# roboskin_distance_IMU_WIFI.net
KiCad netlist of a schematic drawn in EAGLE
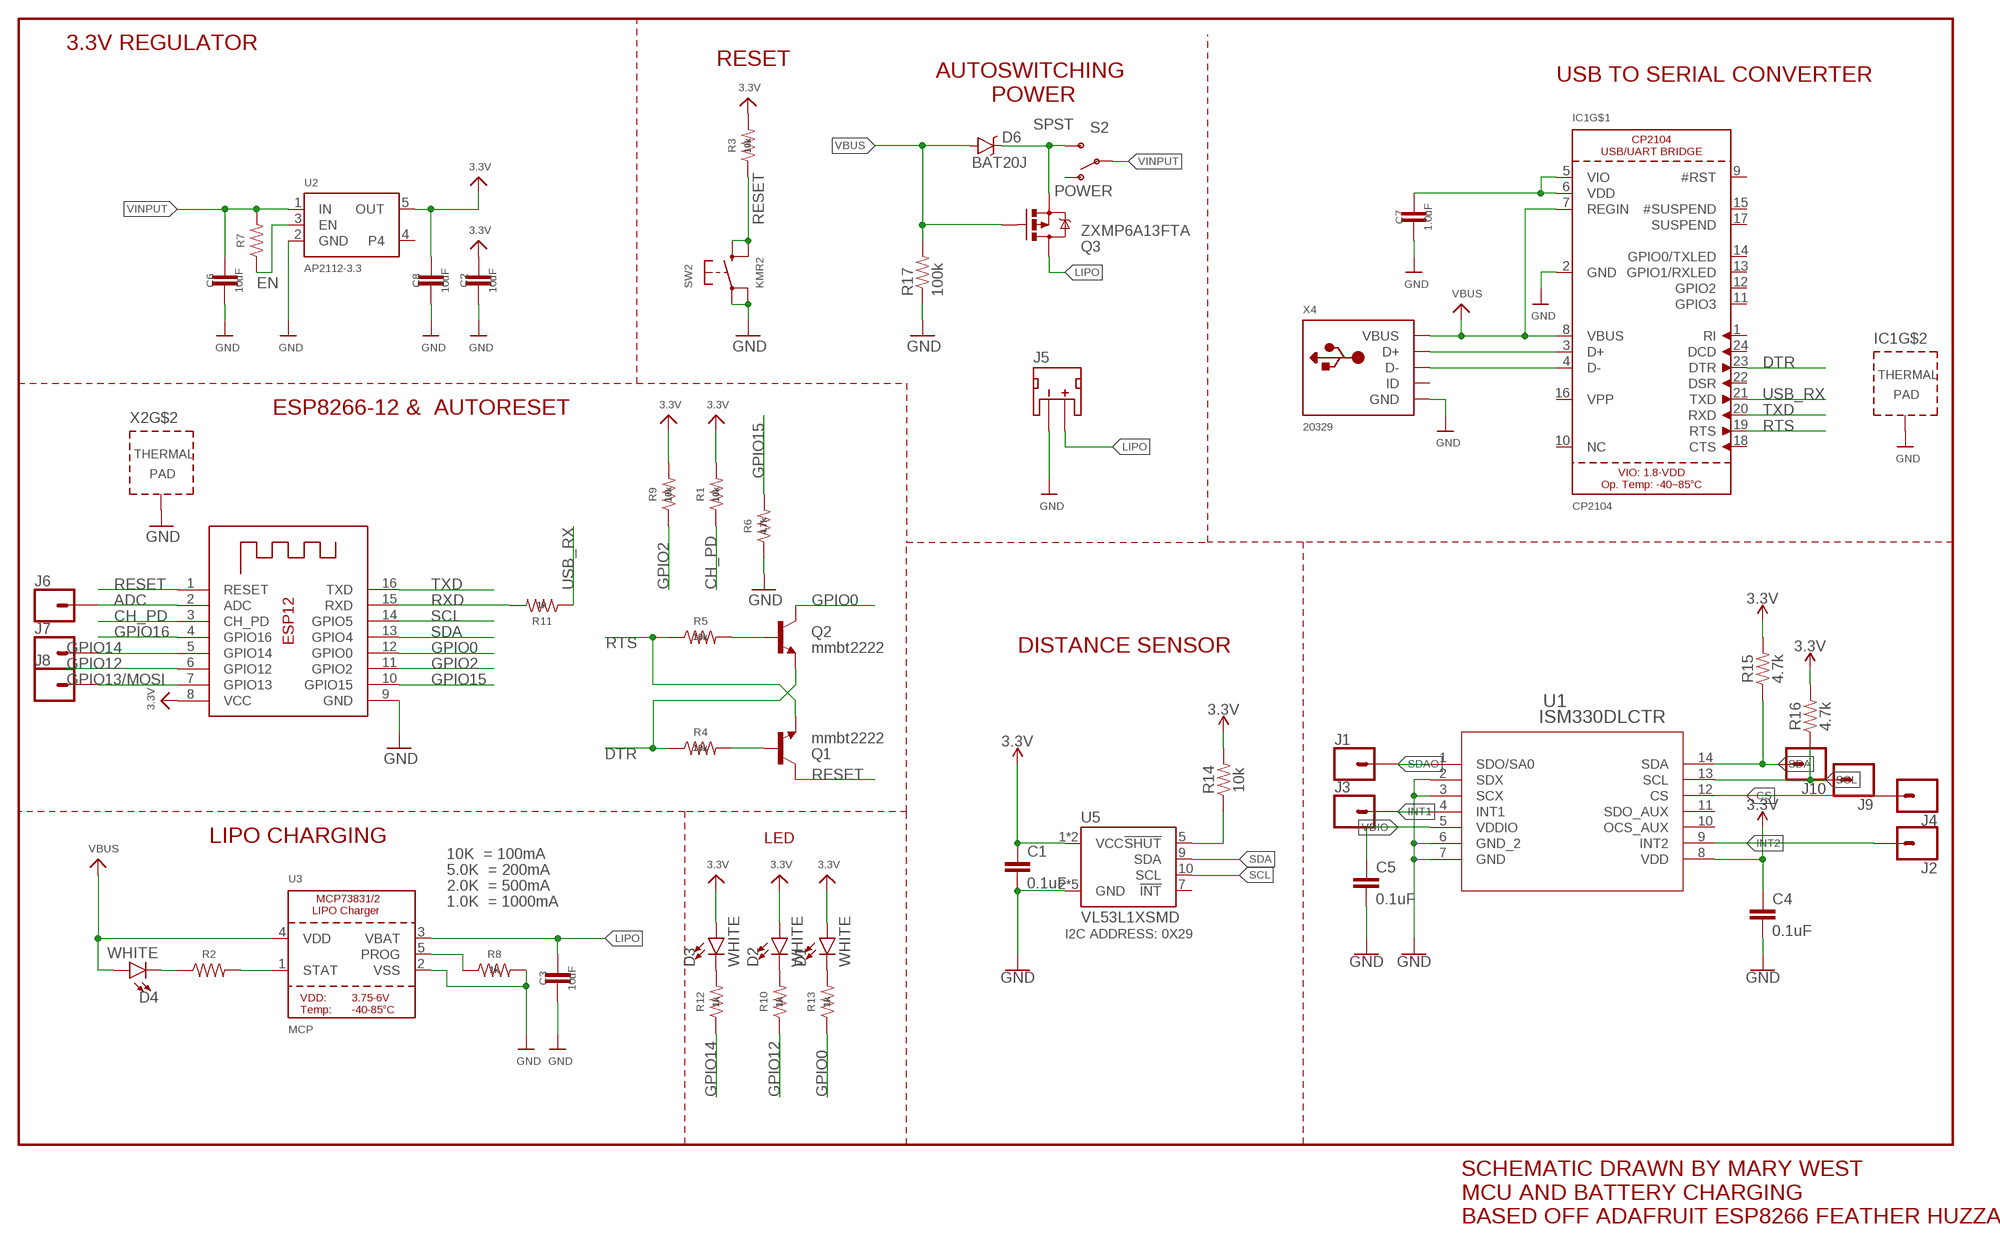
[diagram p0: schematic, sheet 1]

(export (version "E")
  (design (tool "Eeschema 10.0.6"))
  (components
    (comp (ref "C1")
      (value "0.1uF")
      (footprint "eagle-import:0603")
      (libsource (lib "eagle-import") (part "0.1UF-0603-25V-(+80/-20%)"))
    )
    (comp (ref "C2")
      (value "10uF")
      (footprint "eagle-import:0805")
      (libsource (lib "eagle-import") (part "10UF-0805-10V-10%"))
    )
    (comp (ref "C3")
      (value "10uF")
      (footprint "eagle-import:0805")
      (libsource (lib "eagle-import") (part "10UF-0805-10V-10%"))
    )
    (comp (ref "C4")
      (value "0.1uF")
      (footprint "eagle-import:0603")
      (libsource (lib "eagle-import") (part "0.1UF-0603-25V-(+80/-20%)"))
    )
    (comp (ref "C5")
      (value "0.1uF")
      (footprint "eagle-import:0603")
      (libsource (lib "eagle-import") (part "0.1UF-0603-25V-(+80/-20%)"))
    )
    (comp (ref "C6")
      (value "10uF")
      (footprint "eagle-import:0805")
      (libsource (lib "eagle-import") (part "SparkFun-Capacitors_510_10UF-0805-10V-10%"))
    )
    (comp (ref "C7")
      (value "1.0uF")
      (footprint "eagle-import:0603")
      (libsource (lib "eagle-import") (part "1.0UF-0603-16V-10%"))
    )
    (comp (ref "C8")
      (value "10uF")
      (footprint "eagle-import:0805")
      (libsource (lib "eagle-import") (part "10UF-0805-10V-10%"))
    )
    (comp (ref "D1")
      (value "WHITE")
      (footprint "eagle-import:LED-1206")
      (libsource (lib "eagle-import") (part "LED-WHITE1206"))
    )
    (comp (ref "D2")
      (value "WHITE")
      (footprint "eagle-import:LED-1206")
      (libsource (lib "eagle-import") (part "LED-WHITE1206"))
    )
    (comp (ref "D3")
      (value "WHITE")
      (footprint "eagle-import:LED-1206")
      (libsource (lib "eagle-import") (part "LED-WHITE1206"))
    )
    (comp (ref "D4")
      (value "WHITE")
      (footprint "eagle-import:LED-1206")
      (libsource (lib "eagle-import") (part "LED-WHITE1206"))
    )
    (comp (ref "D6")
      (value "BAT20J")
      (footprint "eagle-import:SOD-323")
      (libsource (lib "eagle-import") (part "DIODE-SCHOTTKY-BAT20J"))
    )
    (comp (ref "IC1")
      (value "CP2104")
      (footprint "eagle-import:QFN24_4MM_SMSC")
      (libsource (lib "eagle-import") (part "CP2104"))
    )
    (comp (ref "J1")
      (value "CONN_01")
      (footprint "eagle-import:1X01")
      (libsource (lib "eagle-import") (part "CONN_01"))
    )
    (comp (ref "J2")
      (value "CONN_01")
      (footprint "eagle-import:1X01")
      (libsource (lib "eagle-import") (part "CONN_01"))
    )
    (comp (ref "J3")
      (value "CONN_01")
      (footprint "eagle-import:1X01")
      (libsource (lib "eagle-import") (part "CONN_01"))
    )
    (comp (ref "J4")
      (value "CONN_01")
      (footprint "eagle-import:1X01")
      (libsource (lib "eagle-import") (part "CONN_01"))
    )
    (comp (ref "J5")
      (value "JST_2MM_MALE")
      (footprint "eagle-import:JST-2-SMD")
      (libsource (lib "eagle-import") (part "JST_2MM_MALE"))
    )
    (comp (ref "J6")
      (value "CONN_01")
      (footprint "eagle-import:1X01")
      (libsource (lib "eagle-import") (part "CONN_01"))
    )
    (comp (ref "J7")
      (value "CONN_01")
      (footprint "eagle-import:1X01")
      (libsource (lib "eagle-import") (part "CONN_01"))
    )
    (comp (ref "J8")
      (value "CONN_01")
      (footprint "eagle-import:1X01")
      (libsource (lib "eagle-import") (part "CONN_01"))
    )
    (comp (ref "J9")
      (value "CONN_01")
      (footprint "eagle-import:1X01")
      (libsource (lib "eagle-import") (part "CONN_01"))
    )
    (comp (ref "J10")
      (value "CONN_01")
      (footprint "eagle-import:1X01")
      (libsource (lib "eagle-import") (part "CONN_01"))
    )
    (comp (ref "Q1")
      (value "mmbt2222")
      (footprint "eagle-import:SOT23-3")
      (libsource (lib "eagle-import") (part "TRANSISTOR_NPNSOT23-3"))
    )
    (comp (ref "Q2")
      (value "mmbt2222")
      (footprint "eagle-import:SOT23-3")
      (libsource (lib "eagle-import") (part "TRANSISTOR_NPNSOT23-3"))
    )
    (comp (ref "Q3")
      (value "ZXMP6A13FTA")
      (footprint "eagle-import:SOT23-3")
      (libsource (lib "eagle-import") (part "MOSFET-PCHANNEL"))
    )
    (comp (ref "R1")
      (value "10k")
      (footprint "eagle-import:0603")
      (libsource (lib "eagle-import") (part "SparkFun-Resistors_532_10KOHM-0603-1/10W-1%"))
    )
    (comp (ref "R2")
      (value "1k")
      (footprint "eagle-import:0603")
      (libsource (lib "eagle-import") (part "1KOHM-0603-1/10W-1%"))
    )
    (comp (ref "R3")
      (value "10k")
      (footprint "eagle-import:0603")
      (libsource (lib "eagle-import") (part "SparkFun-Resistors_532_10KOHM-0603-1/10W-1%"))
    )
    (comp (ref "R4")
      (value "10k")
      (footprint "eagle-import:0603")
      (libsource (lib "eagle-import") (part "SparkFun-Resistors_532_10KOHM-0603-1/10W-1%"))
    )
    (comp (ref "R5")
      (value "10k")
      (footprint "eagle-import:0603")
      (libsource (lib "eagle-import") (part "SparkFun-Resistors_532_10KOHM-0603-1/10W-1%"))
    )
    (comp (ref "R6")
      (value "4.7k")
      (footprint "eagle-import:0603")
      (libsource (lib "eagle-import") (part "4.7KOHM-0603-1/10W-1%"))
    )
    (comp (ref "R7")
      (value "10k")
      (footprint "eagle-import:0603")
      (libsource (lib "eagle-import") (part "SparkFun-Resistors_532_10KOHM-0603-1/10W-1%"))
    )
    (comp (ref "R8")
      (value "1k")
      (footprint "eagle-import:0603")
      (libsource (lib "eagle-import") (part "1KOHM-0603-1/10W-1%"))
    )
    (comp (ref "R9")
      (value "10k")
      (footprint "eagle-import:0603")
      (libsource (lib "eagle-import") (part "SparkFun-Resistors_532_10KOHM-0603-1/10W-1%"))
    )
    (comp (ref "R10")
      (value "1k")
      (footprint "eagle-import:0603")
      (libsource (lib "eagle-import") (part "1KOHM-0603-1/10W-1%"))
    )
    (comp (ref "R11")
      (value "1k")
      (footprint "eagle-import:0603")
      (libsource (lib "eagle-import") (part "1KOHM-0603-1/10W-1%"))
    )
    (comp (ref "R12")
      (value "1k")
      (footprint "eagle-import:0603")
      (libsource (lib "eagle-import") (part "1KOHM-0603-1/10W-1%"))
    )
    (comp (ref "R13")
      (value "1k")
      (footprint "eagle-import:0603")
      (libsource (lib "eagle-import") (part "1KOHM-0603-1/10W-1%"))
    )
    (comp (ref "R14")
      (value "10k")
      (footprint "eagle-import:0603")
      (libsource (lib "eagle-import") (part "10KOHM-0603-1/10W-1%"))
    )
    (comp (ref "R15")
      (value "4.7k")
      (footprint "eagle-import:0603")
      (libsource (lib "eagle-import") (part "4.7KOHM-0603-1/10W-1%"))
    )
    (comp (ref "R16")
      (value "4.7k")
      (footprint "eagle-import:0603")
      (libsource (lib "eagle-import") (part "4.7KOHM-0603-1/10W-1%"))
    )
    (comp (ref "R17")
      (value "100k")
      (footprint "eagle-import:0603-RES")
      (libsource (lib "eagle-import") (part "100KOHM-1/10W-1%(0603)"))
    )
    (comp (ref "S2")
      (value "POWER")
      (footprint "eagle-import:SWITCH-SPST-SMD-A")
      (libsource (lib "eagle-import") (part "SWITCH-SPDT-SMD-A"))
    )
    (comp (ref "SW2")
      (value "KMR2")
      (footprint "eagle-import:BTN_KMR2_4.6X2.8")
      (libsource (lib "eagle-import") (part "SWITCH_TACT_SMT4.6X2.8"))
    )
    (comp (ref "U1")
      (value "ISM330DLCTR")
      (footprint "eagle-import:LGA-14L_2P5X3X0P83_STM")
      (fields (field (name "COPYRIGHT") "Copyright (C) 2018 Accelerated Designs. All rights reserved"))
      (libsource (lib "eagle-import") (part "ISM330DLCTR"))
    )
    (comp (ref "U2")
      (value "AP2112-3.3")
      (footprint "eagle-import:SOT23-5")
      (libsource (lib "eagle-import") (part "VREG_SOT23-5"))
    )
    (comp (ref "U3")
      (value "MCP")
      (footprint "eagle-import:SOT23-5")
      (libsource (lib "eagle-import") (part "MCP73831/2"))
    )
    (comp (ref "U5")
      (value "VL53L1XSMD")
      (footprint "eagle-import:VL53L1X")
      (libsource (lib "eagle-import") (part "VL53L1XSMD"))
    )
    (comp (ref "X2")
      (value "ESP-12")
      (footprint "eagle-import:ESP-12S")
      (libsource (lib "eagle-import") (part "ESP-12S"))
    )
    (comp (ref "X4")
      (value "20329")
      (footprint "eagle-import:4UCONN_20329_V2")
      (libsource (lib "eagle-import") (part "USB_MICRO_20329_V2"))
    )
  )
  (nets
    (net (code "1") (name "/ADC") (class "Default")
      (node (ref "J6") (pin "1") (pinfunction "1_1") (pintype "passive"))
      (node (ref "X2") (pin "2") (pinfunction "ADC_2") (pintype "passive"))
    )
    (net (code "2") (name "/CH_PD") (class "Default")
      (node (ref "R1") (pin "1") (pinfunction "1_1") (pintype "passive"))
      (node (ref "X2") (pin "3") (pinfunction "CH_PD_3") (pintype "input"))
    )
    (net (code "3") (name "/DTR") (class "Default")
      (node (ref "IC1") (pin "23") (pinfunction "DTR_23") (pintype "output"))
      (node (ref "Q2") (pin "2") (pinfunction "E_2") (pintype "passive"))
      (node (ref "R4") (pin "1") (pinfunction "1_1") (pintype "passive"))
    )
    (net (code "4") (name "/EN") (class "Default")
      (node (ref "R7") (pin "1") (pinfunction "1_1") (pintype "passive"))
      (node (ref "U2") (pin "3") (pinfunction "EN_3") (pintype "input"))
    )
    (net (code "5") (name "/GPIO0") (class "Default")
      (node (ref "Q2") (pin "3") (pinfunction "C_3") (pintype "passive"))
      (node (ref "R13") (pin "1") (pinfunction "1_1") (pintype "passive"))
      (node (ref "X2") (pin "12") (pinfunction "GPIO0_12") (pintype "bidirectional"))
    )
    (net (code "6") (name "/GPIO2") (class "Default")
      (node (ref "R9") (pin "1") (pinfunction "1_1") (pintype "passive"))
      (node (ref "X2") (pin "11") (pinfunction "GPIO2_11") (pintype "bidirectional"))
    )
    (net (code "7") (name "/GPIO12") (class "Default")
      (node (ref "R10") (pin "1") (pinfunction "1_1") (pintype "passive"))
      (node (ref "X2") (pin "6") (pinfunction "GPIO12_6") (pintype "bidirectional"))
    )
    (net (code "8") (name "/GPIO13{slash}MOSI") (class "Default")
      (node (ref "J8") (pin "1") (pinfunction "1_1") (pintype "passive"))
      (node (ref "X2") (pin "7") (pinfunction "GPIO13_7") (pintype "bidirectional"))
    )
    (net (code "9") (name "/GPIO14") (class "Default")
      (node (ref "J7") (pin "1") (pinfunction "1_1") (pintype "passive"))
      (node (ref "R12") (pin "1") (pinfunction "1_1") (pintype "passive"))
      (node (ref "X2") (pin "5") (pinfunction "GPIO14_5") (pintype "bidirectional"))
    )
    (net (code "10") (name "/GPIO15") (class "Default")
      (node (ref "R6") (pin "2") (pinfunction "2_2") (pintype "passive"))
      (node (ref "X2") (pin "10") (pinfunction "GPIO15_10") (pintype "bidirectional"))
    )
    (net (code "11") (name "/GPIO16") (class "Default")
      (node (ref "X2") (pin "4") (pinfunction "GPIO16_4") (pintype "bidirectional"))
    )
    (net (code "12") (name "/RESET") (class "Default")
      (node (ref "Q1") (pin "3") (pinfunction "C_3") (pintype "passive"))
      (node (ref "R3") (pin "1") (pinfunction "1_1") (pintype "passive"))
      (node (ref "SW2") (pin "B") (pinfunction "S_B") (pintype "passive"))
      (node (ref "SW2") (pin "B'") (pinfunction "S1_B'") (pintype "passive"))
      (node (ref "X2") (pin "1") (pinfunction "RESET_1") (pintype "input"))
    )
    (net (code "13") (name "/RTS") (class "Default")
      (node (ref "IC1") (pin "19") (pinfunction "RTS_19") (pintype "output"))
      (node (ref "Q1") (pin "2") (pinfunction "E_2") (pintype "passive"))
      (node (ref "R5") (pin "1") (pinfunction "1_1") (pintype "passive"))
    )
    (net (code "14") (name "/RXD") (class "Default")
      (node (ref "R11") (pin "2") (pinfunction "2_2") (pintype "passive"))
      (node (ref "X2") (pin "15") (pinfunction "RXD_15") (pintype "input"))
    )
    (net (code "15") (name "/TXD") (class "Default")
      (node (ref "IC1") (pin "20") (pinfunction "RXD_20") (pintype "input"))
      (node (ref "X2") (pin "16") (pinfunction "TXD_16") (pintype "output"))
    )
    (net (code "16") (name "/USB_RX") (class "Default")
      (node (ref "IC1") (pin "21") (pinfunction "TXD_21") (pintype "output"))
      (node (ref "R11") (pin "1") (pinfunction "1_1") (pintype "passive"))
    )
    (net (code "17") (name "3.3V") (class "Default")
      (node (ref "C1") (pin "1") (pinfunction "1_1") (pintype "passive"))
      (node (ref "C2") (pin "1") (pinfunction "1_1") (pintype "passive"))
      (node (ref "C4") (pin "1") (pinfunction "1_1") (pintype "passive"))
      (node (ref "C8") (pin "1") (pinfunction "1_1") (pintype "passive"))
      (node (ref "D1") (pin "A") (pinfunction "A_A") (pintype "passive"))
      (node (ref "D2") (pin "A") (pinfunction "A_A") (pintype "passive"))
      (node (ref "D3") (pin "A") (pinfunction "A_A") (pintype "passive"))
      (node (ref "R1") (pin "2") (pinfunction "2_2") (pintype "passive"))
      (node (ref "R14") (pin "2") (pinfunction "2_2") (pintype "passive"))
      (node (ref "R15") (pin "2") (pinfunction "2_2") (pintype "passive"))
      (node (ref "R16") (pin "2") (pinfunction "2_2") (pintype "passive"))
      (node (ref "R3") (pin "2") (pinfunction "2_2") (pintype "passive"))
      (node (ref "R9") (pin "2") (pinfunction "2_2") (pintype "passive"))
      (node (ref "U1") (pin "8") (pinfunction "VDD_8") (pintype "power_in"))
      (node (ref "U2") (pin "5") (pinfunction "OUT_5") (pintype "power_in"))
      (node (ref "U5") (pin "1") (pinfunction "VCC_1") (pintype "bidirectional"))
      (node (ref "U5") (pin "11") (pinfunction "VCC_11") (pintype "bidirectional"))
      (node (ref "X2") (pin "8") (pinfunction "VCC_8") (pintype "power_in"))
    )
    (net (code "18") (name "CS") (class "Default")
      (node (ref "J4") (pin "1") (pinfunction "1_1") (pintype "passive"))
      (node (ref "U1") (pin "12") (pinfunction "CS_12") (pintype "input"))
    )
    (net (code "19") (name "GND") (class "Default")
      (node (ref "C1") (pin "2") (pinfunction "2_2") (pintype "passive"))
      (node (ref "C2") (pin "2") (pinfunction "2_2") (pintype "passive"))
      (node (ref "C3") (pin "2") (pinfunction "2_2") (pintype "passive"))
      (node (ref "C4") (pin "2") (pinfunction "2_2") (pintype "passive"))
      (node (ref "C5") (pin "2") (pinfunction "2_2") (pintype "passive"))
      (node (ref "C6") (pin "2") (pinfunction "2_2") (pintype "passive"))
      (node (ref "C7") (pin "2") (pinfunction "2_2") (pintype "passive"))
      (node (ref "C8") (pin "2") (pinfunction "2_2") (pintype "passive"))
      (node (ref "IC1") (pin "2") (pinfunction "GND_2") (pintype "power_in"))
      (node (ref "IC1") (pin "THERM") (pinfunction "TP_THERM") (pintype "power_in"))
      (node (ref "J5") (pin "1") (pinfunction "-_1") (pintype "bidirectional"))
      (node (ref "R17") (pin "1") (pinfunction "1_1") (pintype "passive"))
      (node (ref "R6") (pin "1") (pinfunction "1_1") (pintype "passive"))
      (node (ref "R8") (pin "2") (pinfunction "2_2") (pintype "passive"))
      (node (ref "SW2") (pin "A") (pinfunction "P_A") (pintype "passive"))
      (node (ref "SW2") (pin "A'") (pinfunction "P1_A'") (pintype "passive"))
      (node (ref "U1") (pin "2") (pinfunction "SDX_2") (pintype "passive"))
      (node (ref "U1") (pin "3") (pinfunction "SCX_3") (pintype "passive"))
      (node (ref "U1") (pin "6") (pinfunction "GND_2_6") (pintype "passive"))
      (node (ref "U1") (pin "7") (pinfunction "GND_7") (pintype "passive"))
      (node (ref "U2") (pin "2") (pinfunction "GND_2") (pintype "power_in"))
      (node (ref "U3") (pin "2") (pinfunction "VSS_2") (pintype "power_in"))
      (node (ref "U5") (pin "12") (pinfunction "GND_12") (pintype "bidirectional"))
      (node (ref "U5") (pin "2") (pinfunction "GND_2") (pintype "bidirectional"))
      (node (ref "U5") (pin "3") (pinfunction "GND_3") (pintype "bidirectional"))
      (node (ref "U5") (pin "4") (pinfunction "GND_4") (pintype "bidirectional"))
      (node (ref "U5") (pin "6") (pinfunction "GND_6") (pintype "bidirectional"))
      (node (ref "X2") (pin "9") (pinfunction "GND_9") (pintype "power_in"))
      (node (ref "X2") (pin "P$1") (pinfunction "TP_P$1") (pintype "power_in"))
      (node (ref "X4") (pin "BASE@1") (pinfunction "GND_BASE@1") (pintype "power_in"))
      (node (ref "X4") (pin "BASE@2") (pinfunction "GND_BASE@2") (pintype "power_in"))
      (node (ref "X4") (pin "GND") (pinfunction "GND_GND") (pintype "power_in"))
      (node (ref "X4") (pin "SPRT@1") (pinfunction "GND_SPRT@1") (pintype "power_in"))
      (node (ref "X4") (pin "SPRT@2") (pinfunction "GND_SPRT@2") (pintype "power_in"))
      (node (ref "X4") (pin "SPRT@3") (pinfunction "GND_SPRT@3") (pintype "power_in"))
      (node (ref "X4") (pin "SPRT@4") (pinfunction "GND_SPRT@4") (pintype "power_in"))
    )
    (net (code "20") (name "INT1") (class "Default")
      (node (ref "J3") (pin "1") (pinfunction "1_1") (pintype "passive"))
      (node (ref "U1") (pin "4") (pinfunction "INT1_4") (pintype "output"))
    )
    (net (code "21") (name "INT2") (class "Default")
      (node (ref "J2") (pin "1") (pinfunction "1_1") (pintype "passive"))
      (node (ref "U1") (pin "9") (pinfunction "INT2_9") (pintype "output"))
    )
    (net (code "22") (name "LIPO") (class "Default")
      (node (ref "C3") (pin "1") (pinfunction "1_1") (pintype "passive"))
      (node (ref "J5") (pin "2") (pinfunction "+_2") (pintype "bidirectional"))
      (node (ref "Q3") (pin "3") (pinfunction "D_3") (pintype "passive"))
      (node (ref "U3") (pin "3") (pinfunction "VBAT_3") (pintype "power_in"))
    )
    (net (code "23") (name "Net-(D1-PadC)") (class "Default")
      (node (ref "D1") (pin "C") (pinfunction "C_C") (pintype "passive"))
      (node (ref "R13") (pin "2") (pinfunction "2_2") (pintype "passive"))
    )
    (net (code "24") (name "Net-(D2-PadC)") (class "Default")
      (node (ref "D2") (pin "C") (pinfunction "C_C") (pintype "passive"))
      (node (ref "R10") (pin "2") (pinfunction "2_2") (pintype "passive"))
    )
    (net (code "25") (name "Net-(D3-PadC)") (class "Default")
      (node (ref "D3") (pin "C") (pinfunction "C_C") (pintype "passive"))
      (node (ref "R12") (pin "2") (pinfunction "2_2") (pintype "passive"))
    )
    (net (code "26") (name "Net-(D4-PadC)") (class "Default")
      (node (ref "D4") (pin "C") (pinfunction "C_C") (pintype "passive"))
      (node (ref "R2") (pin "1") (pinfunction "1_1") (pintype "passive"))
    )
    (net (code "27") (name "Net-(IC1A-D+)") (class "Default")
      (node (ref "IC1") (pin "3") (pinfunction "D+_3") (pintype "bidirectional"))
      (node (ref "X4") (pin "D+") (pinfunction "D+_D+") (pintype "bidirectional"))
    )
    (net (code "28") (name "Net-(IC1A-D-)") (class "Default")
      (node (ref "IC1") (pin "4") (pinfunction "D-_4") (pintype "bidirectional"))
      (node (ref "X4") (pin "D-") (pinfunction "D-_D-") (pintype "bidirectional"))
    )
    (net (code "29") (name "Net-(IC1A-VDD)") (class "Default")
      (node (ref "C7") (pin "1") (pinfunction "1_1") (pintype "passive"))
      (node (ref "IC1") (pin "5") (pinfunction "VIO_5") (pintype "power_in"))
      (node (ref "IC1") (pin "6") (pinfunction "VDD_6") (pintype "power_in"))
    )
    (net (code "30") (name "Net-(Q1-B)") (class "Default")
      (node (ref "Q1") (pin "1") (pinfunction "B_1") (pintype "passive"))
      (node (ref "R4") (pin "2") (pinfunction "2_2") (pintype "passive"))
    )
    (net (code "31") (name "Net-(Q2-B)") (class "Default")
      (node (ref "Q2") (pin "1") (pinfunction "B_1") (pintype "passive"))
      (node (ref "R5") (pin "2") (pinfunction "2_2") (pintype "passive"))
    )
    (net (code "32") (name "Net-(Q3-S)") (class "Default")
      (node (ref "D6") (pin "C") (pinfunction "C_C") (pintype "passive"))
      (node (ref "Q3") (pin "2") (pinfunction "S_2") (pintype "passive"))
      (node (ref "S2") (pin "3") (pinfunction "S_3") (pintype "passive"))
    )
    (net (code "33") (name "Net-(U3-PROG)") (class "Default")
      (node (ref "R8") (pin "1") (pinfunction "1_1") (pintype "passive"))
      (node (ref "U3") (pin "5") (pinfunction "PROG_5") (pintype "input"))
    )
    (net (code "34") (name "Net-(U3-STAT)") (class "Default")
      (node (ref "R2") (pin "2") (pinfunction "2_2") (pintype "passive"))
      (node (ref "U3") (pin "1") (pinfunction "STAT_1") (pintype "output"))
    )
    (net (code "35") (name "Net-(U5-~{SHUT})") (class "Default")
      (node (ref "R14") (pin "1") (pinfunction "1_1") (pintype "passive"))
      (node (ref "U5") (pin "5") (pinfunction "~{SHUT}_5") (pintype "bidirectional"))
    )
    (net (code "36") (name "SCL") (class "Default")
      (node (ref "J9") (pin "1") (pinfunction "1_1") (pintype "passive"))
      (node (ref "R16") (pin "1") (pinfunction "1_1") (pintype "passive"))
      (node (ref "U1") (pin "13") (pinfunction "SCL_13") (pintype "input"))
      (node (ref "U5") (pin "10") (pinfunction "SCL_10") (pintype "bidirectional"))
      (node (ref "X2") (pin "14") (pinfunction "GPIO5_14") (pintype "bidirectional"))
    )
    (net (code "37") (name "SDA") (class "Default")
      (node (ref "J10") (pin "1") (pinfunction "1_1") (pintype "passive"))
      (node (ref "R15") (pin "1") (pinfunction "1_1") (pintype "passive"))
      (node (ref "U1") (pin "14") (pinfunction "SDA_14") (pintype "bidirectional"))
      (node (ref "U5") (pin "9") (pinfunction "SDA_9") (pintype "bidirectional"))
      (node (ref "X2") (pin "13") (pinfunction "GPIO4_13") (pintype "bidirectional"))
    )
    (net (code "38") (name "SDAO") (class "Default")
      (node (ref "J1") (pin "1") (pinfunction "1_1") (pintype "passive"))
      (node (ref "U1") (pin "1") (pinfunction "SDO/SA0_1") (pintype "bidirectional"))
    )
    (net (code "39") (name "VBUS") (class "Default")
      (node (ref "D4") (pin "A") (pinfunction "A_A") (pintype "passive"))
      (node (ref "D6") (pin "A") (pinfunction "A_A") (pintype "passive"))
      (node (ref "IC1") (pin "7") (pinfunction "REGIN_7") (pintype "power_in"))
      (node (ref "IC1") (pin "8") (pinfunction "VBUS_8") (pintype "power_in"))
      (node (ref "Q3") (pin "1") (pinfunction "G_1") (pintype "passive"))
      (node (ref "R17") (pin "2") (pinfunction "2_2") (pintype "passive"))
      (node (ref "U3") (pin "4") (pinfunction "VDD_4") (pintype "power_in"))
      (node (ref "X4") (pin "VBUS") (pinfunction "VBUS_VBUS") (pintype "power_in"))
    )
    (net (code "40") (name "VDIO") (class "Default")
      (node (ref "C5") (pin "1") (pinfunction "1_1") (pintype "passive"))
      (node (ref "U1") (pin "5") (pinfunction "VDDIO_5") (pintype "power_in"))
    )
    (net (code "41") (name "VINPUT") (class "Default")
      (node (ref "C6") (pin "1") (pinfunction "1_1") (pintype "passive"))
      (node (ref "R7") (pin "2") (pinfunction "2_2") (pintype "passive"))
      (node (ref "S2") (pin "2") (pinfunction "P_2") (pintype "passive"))
      (node (ref "U2") (pin "1") (pinfunction "IN_1") (pintype "power_in"))
    )
    (net (code "42") (name "unconnected-(IC1A-#RST-Pad9)") (class "Default")
      (node (ref "IC1") (pin "9") (pinfunction "#RST_9") (pintype "bidirectional"))
    )
    (net (code "43") (name "unconnected-(IC1A-#SUSPEND-Pad15)") (class "Default")
      (node (ref "IC1") (pin "15") (pinfunction "#SUSPEND_15") (pintype "output"))
    )
    (net (code "44") (name "unconnected-(IC1A-CTS-Pad18)") (class "Default")
      (node (ref "IC1") (pin "18") (pinfunction "CTS_18") (pintype "input"))
    )
    (net (code "45") (name "unconnected-(IC1A-DCD-Pad24)") (class "Default")
      (node (ref "IC1") (pin "24") (pinfunction "DCD_24") (pintype "input"))
    )
    (net (code "46") (name "unconnected-(IC1A-DSR-Pad22)") (class "Default")
      (node (ref "IC1") (pin "22") (pinfunction "DSR_22") (pintype "input"))
    )
    (net (code "47") (name "unconnected-(IC1A-GPIO0{slash}TXLED-Pad14)") (class "Default")
      (node (ref "IC1") (pin "14") (pinfunction "GPIO0/TXLED_14") (pintype "bidirectional"))
    )
    (net (code "48") (name "unconnected-(IC1A-GPIO1{slash}RXLED-Pad13)") (class "Default")
      (node (ref "IC1") (pin "13") (pinfunction "GPIO1/RXLED_13") (pintype "bidirectional"))
    )
    (net (code "49") (name "unconnected-(IC1A-GPIO2-Pad12)") (class "Default")
      (node (ref "IC1") (pin "12") (pinfunction "GPIO2_12") (pintype "bidirectional"))
    )
    (net (code "50") (name "unconnected-(IC1A-GPIO3-Pad11)") (class "Default")
      (node (ref "IC1") (pin "11") (pinfunction "GPIO3_11") (pintype "bidirectional"))
    )
    (net (code "51") (name "unconnected-(IC1A-NC-Pad10)") (class "Default")
      (node (ref "IC1") (pin "10") (pinfunction "NC_10") (pintype "no_connect"))
    )
    (net (code "52") (name "unconnected-(IC1A-RI-Pad1)") (class "Default")
      (node (ref "IC1") (pin "1") (pinfunction "RI_1") (pintype "input"))
    )
    (net (code "53") (name "unconnected-(IC1A-SUSPEND-Pad17)") (class "Default")
      (node (ref "IC1") (pin "17") (pinfunction "SUSPEND_17") (pintype "output"))
    )
    (net (code "54") (name "unconnected-(IC1A-VPP-Pad16)") (class "Default")
      (node (ref "IC1") (pin "16") (pinfunction "VPP_16") (pintype "bidirectional"))
    )
    (net (code "55") (name "unconnected-(J5-PAD1-PadNC1)") (class "Default")
      (node (ref "J5") (pin "NC1") (pinfunction "PAD1_NC1") (pintype "bidirectional"))
    )
    (net (code "56") (name "unconnected-(J5-PAD2-PadNC2)") (class "Default")
      (node (ref "J5") (pin "NC2") (pinfunction "PAD2_NC2") (pintype "bidirectional"))
    )
    (net (code "57") (name "unconnected-(S2-O-Pad1)") (class "Default")
      (node (ref "S2") (pin "1") (pinfunction "O_1") (pintype "passive"))
    )
    (net (code "58") (name "unconnected-(U1-OCS_AUX-Pad10)") (class "Default")
      (node (ref "U1") (pin "10") (pinfunction "OCS_AUX_10") (pintype "passive"))
    )
    (net (code "59") (name "unconnected-(U1-SDO_AUX-Pad11)") (class "Default")
      (node (ref "U1") (pin "11") (pinfunction "SDO_AUX_11") (pintype "passive"))
    )
    (net (code "60") (name "unconnected-(U2-P4-Pad4)") (class "Default")
      (node (ref "U2") (pin "4") (pinfunction "P4_4") (pintype "bidirectional"))
    )
    (net (code "61") (name "unconnected-(U5-~{INT}-Pad7)") (class "Default")
      (node (ref "U5") (pin "7") (pinfunction "~{INT}_7") (pintype "bidirectional"))
    )
    (net (code "62") (name "unconnected-(X4-PadID)") (class "Default")
      (node (ref "X4") (pin "ID") (pinfunction "ID_ID") (pintype "bidirectional"))
    )
  )
)
